# Keyfinder_TinyK20.net
KiCad netlist of a schematic drawn in Altium Designer
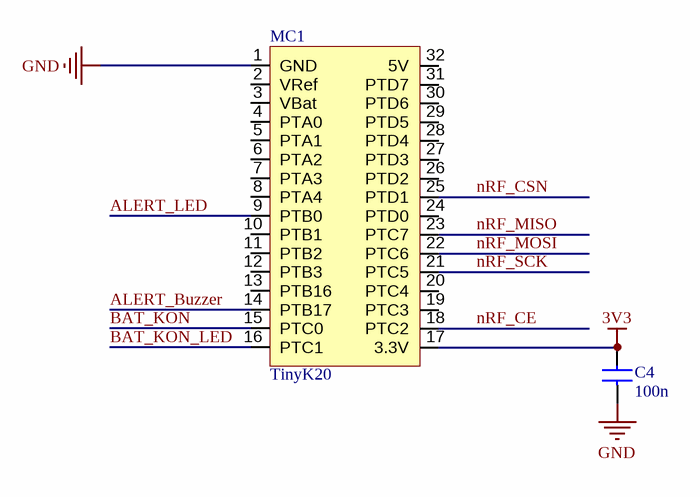
[diagram p0: Keyfinder_TinyK20.SchDoc]

(export (version "E")
  (design (tool "Eeschema 10.0.6"))
  (components
    (comp (ref "C4")
      (value "100n")
      (footprint "0805_C")
      (description "Normaler Kondensator")
      (libsource (lib "MainBoard") (part "C?"))
    )
    (comp (ref "MC1") (value "TinyK20") (footprint "DIP32") (libsource (lib "MainBoard") (part "TinyK20")))
  )
  (nets
    (net (code "1") (name "/ALERT_Buzzer") (class "Default")
      (node (ref "MC1") (pin "14") (pinfunction "PTB17_14") (pintype "passive"))
    )
    (net (code "2") (name "/ALERT_LED") (class "Default")
      (node (ref "MC1") (pin "9") (pinfunction "PTB0_9") (pintype "passive"))
    )
    (net (code "3") (name "/BAT_KON") (class "Default")
      (node (ref "MC1") (pin "15") (pinfunction "PTC0_15") (pintype "passive"))
    )
    (net (code "4") (name "/BAT_KON_LED") (class "Default")
      (node (ref "MC1") (pin "16") (pinfunction "PTC1_16") (pintype "passive"))
    )
    (net (code "5") (name "/nRF_CE") (class "Default")
      (node (ref "MC1") (pin "18") (pinfunction "PTC2_18") (pintype "passive"))
    )
    (net (code "6") (name "/nRF_CSN") (class "Default")
      (node (ref "MC1") (pin "25") (pinfunction "PTD1_25") (pintype "passive"))
    )
    (net (code "7") (name "/nRF_MISO") (class "Default")
      (node (ref "MC1") (pin "23") (pinfunction "PTC7_23") (pintype "passive"))
    )
    (net (code "8") (name "/nRF_MOSI") (class "Default")
      (node (ref "MC1") (pin "22") (pinfunction "PTC6_22") (pintype "passive"))
    )
    (net (code "9") (name "/nRF_SCK") (class "Default")
      (node (ref "MC1") (pin "21") (pinfunction "PTC5_21") (pintype "passive"))
    )
    (net (code "10") (name "3V3") (class "Default")
      (node (ref "C4") (pin "2") (pinfunction "2_2") (pintype "passive"))
      (node (ref "MC1") (pin "17") (pinfunction "3.3V_17") (pintype "passive"))
    )
    (net (code "11") (name "GND") (class "Default")
      (node (ref "C4") (pin "1") (pinfunction "1_1") (pintype "passive"))
      (node (ref "MC1") (pin "1") (pinfunction "GND_1") (pintype "passive"))
    )
    (net (code "12") (name "unconnected-(MC1-5V-Pad32)") (class "Default")
      (node (ref "MC1") (pin "32") (pinfunction "5V_32") (pintype "passive"))
    )
    (net (code "13") (name "unconnected-(MC1-PTA0-Pad4)") (class "Default")
      (node (ref "MC1") (pin "4") (pinfunction "PTA0_4") (pintype "passive"))
    )
    (net (code "14") (name "unconnected-(MC1-PTA1-Pad5)") (class "Default")
      (node (ref "MC1") (pin "5") (pinfunction "PTA1_5") (pintype "passive"))
    )
    (net (code "15") (name "unconnected-(MC1-PTA2-Pad6)") (class "Default")
      (node (ref "MC1") (pin "6") (pinfunction "PTA2_6") (pintype "passive"))
    )
    (net (code "16") (name "unconnected-(MC1-PTA3-Pad7)") (class "Default")
      (node (ref "MC1") (pin "7") (pinfunction "PTA3_7") (pintype "passive"))
    )
    (net (code "17") (name "unconnected-(MC1-PTA4-Pad8)") (class "Default")
      (node (ref "MC1") (pin "8") (pinfunction "PTA4_8") (pintype "passive"))
    )
    (net (code "18") (name "unconnected-(MC1-PTB1-Pad10)") (class "Default")
      (node (ref "MC1") (pin "10") (pinfunction "PTB1_10") (pintype "passive"))
    )
    (net (code "19") (name "unconnected-(MC1-PTB2-Pad11)") (class "Default")
      (node (ref "MC1") (pin "11") (pinfunction "PTB2_11") (pintype "passive"))
    )
    (net (code "20") (name "unconnected-(MC1-PTB3-Pad12)") (class "Default")
      (node (ref "MC1") (pin "12") (pinfunction "PTB3_12") (pintype "passive"))
    )
    (net (code "21") (name "unconnected-(MC1-PTB16-Pad13)") (class "Default")
      (node (ref "MC1") (pin "13") (pinfunction "PTB16_13") (pintype "passive"))
    )
    (net (code "22") (name "unconnected-(MC1-PTC3-Pad19)") (class "Default")
      (node (ref "MC1") (pin "19") (pinfunction "PTC3_19") (pintype "passive"))
    )
    (net (code "23") (name "unconnected-(MC1-PTC4-Pad20)") (class "Default")
      (node (ref "MC1") (pin "20") (pinfunction "PTC4_20") (pintype "passive"))
    )
    (net (code "24") (name "unconnected-(MC1-PTD0-Pad24)") (class "Default")
      (node (ref "MC1") (pin "24") (pinfunction "PTD0_24") (pintype "passive"))
    )
    (net (code "25") (name "unconnected-(MC1-PTD2-Pad26)") (class "Default")
      (node (ref "MC1") (pin "26") (pinfunction "PTD2_26") (pintype "passive"))
    )
    (net (code "26") (name "unconnected-(MC1-PTD3-Pad27)") (class "Default")
      (node (ref "MC1") (pin "27") (pinfunction "PTD3_27") (pintype "passive"))
    )
    (net (code "27") (name "unconnected-(MC1-PTD4-Pad28)") (class "Default")
      (node (ref "MC1") (pin "28") (pinfunction "PTD4_28") (pintype "passive"))
    )
    (net (code "28") (name "unconnected-(MC1-PTD5-Pad29)") (class "Default")
      (node (ref "MC1") (pin "29") (pinfunction "PTD5_29") (pintype "passive"))
    )
    (net (code "29") (name "unconnected-(MC1-PTD6-Pad30)") (class "Default")
      (node (ref "MC1") (pin "30") (pinfunction "PTD6_30") (pintype "passive"))
    )
    (net (code "30") (name "unconnected-(MC1-PTD7-Pad31)") (class "Default")
      (node (ref "MC1") (pin "31") (pinfunction "PTD7_31") (pintype "passive"))
    )
    (net (code "31") (name "unconnected-(MC1-VBat-Pad3)") (class "Default")
      (node (ref "MC1") (pin "3") (pinfunction "VBat_3") (pintype "passive"))
    )
    (net (code "32") (name "unconnected-(MC1-VRef-Pad2)") (class "Default")
      (node (ref "MC1") (pin "2") (pinfunction "VRef_2") (pintype "passive"))
    )
  )
)
